# soic8.net
KiCad netlist of a schematic drawn in EAGLE
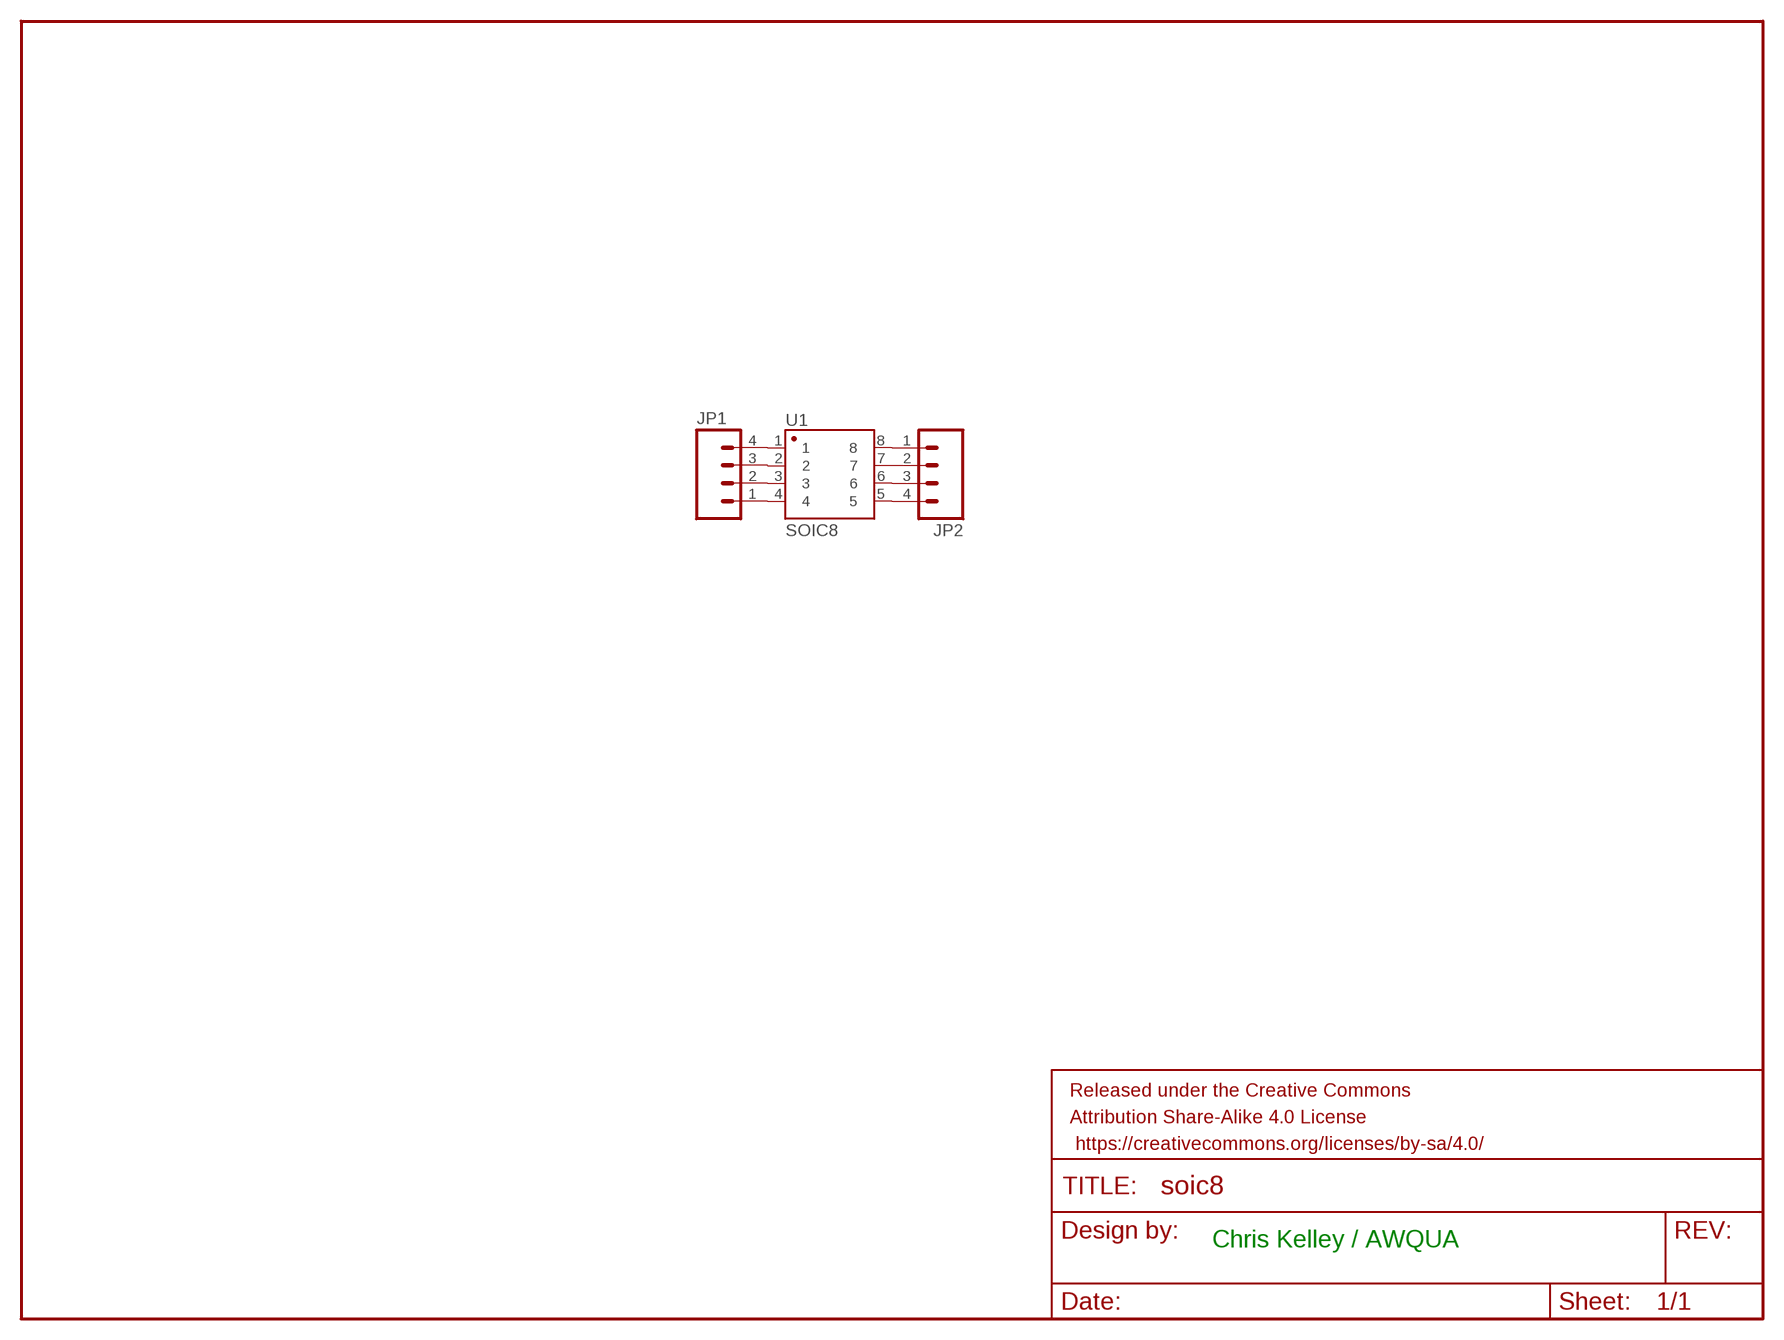
[diagram p0: schematic, sheet 1]

(export (version "E")
  (design (tool "Eeschema 10.0.6"))
  (components
    (comp (ref "FRAME1")
      (value "FRAME-LETTER")
      (footprint "eagle-import:CREATIVE_COMMONS")
      (libsource (lib "eagle-import") (part "FRAME-LETTER"))
    )
    (comp (ref "JP1")
      (value "M04PTH")
      (footprint "eagle-import:1X04")
      (libsource (lib "eagle-import") (part "M04PTH"))
    )
    (comp (ref "JP2")
      (value "M04PTH")
      (footprint "eagle-import:1X04")
      (libsource (lib "eagle-import") (part "M04PTH"))
    )
    (comp (ref "U1")
      (value "SOIC8")
      (footprint "eagle-import:SO08-UNIVERSAL")
      (libsource (lib "eagle-import") (part "GENERIC-SOIC8"))
    )
  )
  (nets
    (net (code "1") (name "Net-(JP1-Pad1)") (class "Default")
      (node (ref "JP1") (pin "1") (pinfunction "1_1") (pintype "passive"))
      (node (ref "U1") (pin "4") (pinfunction "4_4") (pintype "bidirectional"))
    )
    (net (code "2") (name "Net-(JP1-Pad2)") (class "Default")
      (node (ref "JP1") (pin "2") (pinfunction "2_2") (pintype "passive"))
      (node (ref "U1") (pin "3") (pinfunction "3_3") (pintype "bidirectional"))
    )
    (net (code "3") (name "Net-(JP1-Pad3)") (class "Default")
      (node (ref "JP1") (pin "3") (pinfunction "3_3") (pintype "passive"))
      (node (ref "U1") (pin "2") (pinfunction "2_2") (pintype "bidirectional"))
    )
    (net (code "4") (name "Net-(JP1-Pad4)") (class "Default")
      (node (ref "JP1") (pin "4") (pinfunction "4_4") (pintype "passive"))
      (node (ref "U1") (pin "1") (pinfunction "1_1") (pintype "bidirectional"))
    )
    (net (code "5") (name "Net-(JP2-Pad1)") (class "Default")
      (node (ref "JP2") (pin "1") (pinfunction "1_1") (pintype "passive"))
      (node (ref "U1") (pin "8") (pinfunction "8_8") (pintype "bidirectional"))
    )
    (net (code "6") (name "Net-(JP2-Pad2)") (class "Default")
      (node (ref "JP2") (pin "2") (pinfunction "2_2") (pintype "passive"))
      (node (ref "U1") (pin "7") (pinfunction "7_7") (pintype "bidirectional"))
    )
    (net (code "7") (name "Net-(JP2-Pad3)") (class "Default")
      (node (ref "JP2") (pin "3") (pinfunction "3_3") (pintype "passive"))
      (node (ref "U1") (pin "6") (pinfunction "6_6") (pintype "bidirectional"))
    )
    (net (code "8") (name "Net-(JP2-Pad4)") (class "Default")
      (node (ref "JP2") (pin "4") (pinfunction "4_4") (pintype "passive"))
      (node (ref "U1") (pin "5") (pinfunction "5_5") (pintype "bidirectional"))
    )
  )
)
